# Arduino_Nano_with_7_segment_display.net
KiCad netlist of a schematic drawn in EAGLE
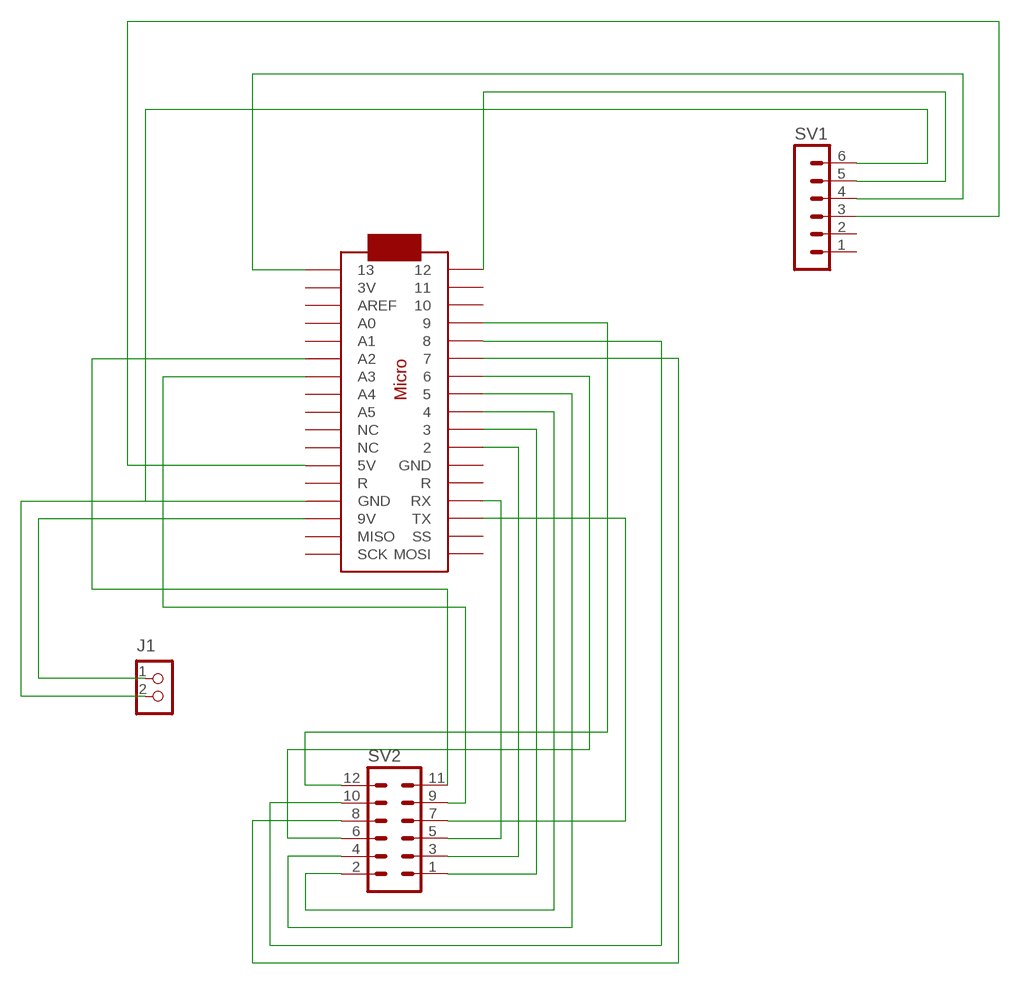
[diagram p0: schematic, sheet 1]

(export (version "E")
  (design (tool "Eeschema 10.0.6"))
  (components
    (comp (ref "J1")
      (value "CON_TERMINAL_BLOCK_02-5MM")
      (footprint "eagle-import:TERMINAL_BLOCK_2P_5")
      (libsource (lib "eagle-import") (part "CON_TERMINAL_BLOCK_02-5MM"))
    )
    (comp (ref "SV1")
      (value "MA06-1")
      (footprint "eagle-import:MA06-1")
      (libsource (lib "eagle-import") (part "MA06-1"))
    )
    (comp (ref "SV2")
      (value "MA06-2")
      (footprint "eagle-import:MA06-2")
      (libsource (lib "eagle-import") (part "MA06-2"))
    )
    (comp (ref "U$1")
      (value "ARDUINOMICRO")
      (footprint "eagle-import:ARDUINOMICRO")
      (libsource (lib "eagle-import") (part "ARDUINOMICRO"))
    )
  )
  (nets
    (net (code "1") (name "Net-(J1-Pad2)") (class "Default")
      (node (ref "J1") (pin "2") (pinfunction "2_2") (pintype "passive"))
      (node (ref "SV1") (pin "6") (pinfunction "6_6") (pintype "passive"))
      (node (ref "U$1") (pin "P$12") (pinfunction "GND_P$12") (pintype "bidirectional"))
    )
    (net (code "2") (name "Net-(U$1-2)") (class "Default")
      (node (ref "SV2") (pin "3") (pinfunction "3_3") (pintype "passive"))
      (node (ref "U$1") (pin "P$11") (pinfunction "2_P$11") (pintype "bidirectional"))
    )
    (net (code "3") (name "Net-(U$1-3)") (class "Default")
      (node (ref "SV2") (pin "1") (pinfunction "1_1") (pintype "passive"))
      (node (ref "U$1") (pin "P$10") (pinfunction "3_P$10") (pintype "bidirectional"))
    )
    (net (code "4") (name "Net-(U$1-4)") (class "Default")
      (node (ref "SV2") (pin "2") (pinfunction "2_2") (pintype "passive"))
      (node (ref "U$1") (pin "P$9") (pinfunction "4_P$9") (pintype "bidirectional"))
    )
    (net (code "5") (name "Net-(U$1-5)") (class "Default")
      (node (ref "SV2") (pin "4") (pinfunction "4_4") (pintype "passive"))
      (node (ref "U$1") (pin "P$8") (pinfunction "5_P$8") (pintype "bidirectional"))
    )
    (net (code "6") (name "Net-(U$1-5V)") (class "Default")
      (node (ref "SV1") (pin "3") (pinfunction "3_3") (pintype "passive"))
      (node (ref "U$1") (pin "P$23") (pinfunction "5V_P$23") (pintype "bidirectional"))
    )
    (net (code "7") (name "Net-(U$1-6)") (class "Default")
      (node (ref "SV2") (pin "6") (pinfunction "6_6") (pintype "passive"))
      (node (ref "U$1") (pin "P$7") (pinfunction "6_P$7") (pintype "bidirectional"))
    )
    (net (code "8") (name "Net-(U$1-7)") (class "Default")
      (node (ref "SV2") (pin "8") (pinfunction "8_8") (pintype "passive"))
      (node (ref "U$1") (pin "P$6") (pinfunction "7_P$6") (pintype "bidirectional"))
    )
    (net (code "9") (name "Net-(U$1-8)") (class "Default")
      (node (ref "SV2") (pin "10") (pinfunction "10_10") (pintype "passive"))
      (node (ref "U$1") (pin "P$5") (pinfunction "8_P$5") (pintype "bidirectional"))
    )
    (net (code "10") (name "Net-(U$1-9)") (class "Default")
      (node (ref "SV2") (pin "12") (pinfunction "12_12") (pintype "passive"))
      (node (ref "U$1") (pin "P$4") (pinfunction "9_P$4") (pintype "bidirectional"))
    )
    (net (code "11") (name "Net-(U$1-9V)") (class "Default")
      (node (ref "J1") (pin "1") (pinfunction "1_1") (pintype "passive"))
      (node (ref "U$1") (pin "P$20") (pinfunction "9V_P$20") (pintype "bidirectional"))
    )
    (net (code "12") (name "Net-(U$1-12)") (class "Default")
      (node (ref "SV1") (pin "5") (pinfunction "5_5") (pintype "passive"))
      (node (ref "U$1") (pin "P$1") (pinfunction "12_P$1") (pintype "bidirectional"))
    )
    (net (code "13") (name "Net-(U$1-13)") (class "Default")
      (node (ref "SV1") (pin "4") (pinfunction "4_4") (pintype "passive"))
      (node (ref "U$1") (pin "P$34") (pinfunction "13_P$34") (pintype "bidirectional"))
    )
    (net (code "14") (name "Net-(U$1-A2)") (class "Default")
      (node (ref "SV2") (pin "11") (pinfunction "11_11") (pintype "passive"))
      (node (ref "U$1") (pin "P$29") (pinfunction "A2_P$29") (pintype "bidirectional"))
    )
    (net (code "15") (name "Net-(U$1-A3)") (class "Default")
      (node (ref "SV2") (pin "9") (pinfunction "9_9") (pintype "passive"))
      (node (ref "U$1") (pin "P$28") (pinfunction "A3_P$28") (pintype "bidirectional"))
    )
    (net (code "16") (name "Net-(U$1-RX)") (class "Default")
      (node (ref "SV2") (pin "5") (pinfunction "5_5") (pintype "passive"))
      (node (ref "U$1") (pin "P$14") (pinfunction "RX_P$14") (pintype "bidirectional"))
    )
    (net (code "17") (name "Net-(U$1-TX)") (class "Default")
      (node (ref "SV2") (pin "7") (pinfunction "7_7") (pintype "passive"))
      (node (ref "U$1") (pin "P$15") (pinfunction "TX_P$15") (pintype "bidirectional"))
    )
    (net (code "18") (name "unconnected-(SV1-Pad1)") (class "Default")
      (node (ref "SV1") (pin "1") (pinfunction "1_1") (pintype "passive"))
    )
    (net (code "19") (name "unconnected-(SV1-Pad2)") (class "Default")
      (node (ref "SV1") (pin "2") (pinfunction "2_2") (pintype "passive"))
    )
    (net (code "20") (name "unconnected-(U$1-3V-PadP$33)") (class "Default")
      (node (ref "U$1") (pin "P$33") (pinfunction "3V_P$33") (pintype "bidirectional"))
    )
    (net (code "21") (name "unconnected-(U$1-10-PadP$3)") (class "Default")
      (node (ref "U$1") (pin "P$3") (pinfunction "10_P$3") (pintype "bidirectional"))
    )
    (net (code "22") (name "unconnected-(U$1-11-PadP$2)") (class "Default")
      (node (ref "U$1") (pin "P$2") (pinfunction "11_P$2") (pintype "bidirectional"))
    )
    (net (code "23") (name "unconnected-(U$1-A0-PadP$31)") (class "Default")
      (node (ref "U$1") (pin "P$31") (pinfunction "A0_P$31") (pintype "bidirectional"))
    )
    (net (code "24") (name "unconnected-(U$1-A1-PadP$30)") (class "Default")
      (node (ref "U$1") (pin "P$30") (pinfunction "A1_P$30") (pintype "bidirectional"))
    )
    (net (code "25") (name "unconnected-(U$1-A4-PadP$27)") (class "Default")
      (node (ref "U$1") (pin "P$27") (pinfunction "A4_P$27") (pintype "bidirectional"))
    )
    (net (code "26") (name "unconnected-(U$1-A5-PadP$26)") (class "Default")
      (node (ref "U$1") (pin "P$26") (pinfunction "A5_P$26") (pintype "bidirectional"))
    )
    (net (code "27") (name "unconnected-(U$1-AREF-PadP$32)") (class "Default")
      (node (ref "U$1") (pin "P$32") (pinfunction "AREF_P$32") (pintype "bidirectional"))
    )
    (net (code "28") (name "unconnected-(U$1-GND-PadP$21)") (class "Default")
      (node (ref "U$1") (pin "P$21") (pinfunction "GND_P$21") (pintype "bidirectional"))
    )
    (net (code "29") (name "unconnected-(U$1-MISO-PadP$19)") (class "Default")
      (node (ref "U$1") (pin "P$19") (pinfunction "MISO_P$19") (pintype "bidirectional"))
    )
    (net (code "30") (name "unconnected-(U$1-MOSI-PadP$17)") (class "Default")
      (node (ref "U$1") (pin "P$17") (pinfunction "MOSI_P$17") (pintype "bidirectional"))
    )
    (net (code "31") (name "unconnected-(U$1-NC-PadP$24)") (class "Default")
      (node (ref "U$1") (pin "P$24") (pinfunction "NC_P$24") (pintype "bidirectional"))
    )
    (net (code "32") (name "unconnected-(U$1-NC-PadP$25)") (class "Default")
      (node (ref "U$1") (pin "P$25") (pinfunction "NC_P$25") (pintype "bidirectional"))
    )
    (net (code "33") (name "unconnected-(U$1-R-PadP$13)") (class "Default")
      (node (ref "U$1") (pin "P$13") (pinfunction "R_P$13") (pintype "bidirectional"))
    )
    (net (code "34") (name "unconnected-(U$1-R-PadP$22)") (class "Default")
      (node (ref "U$1") (pin "P$22") (pinfunction "R_P$22") (pintype "bidirectional"))
    )
    (net (code "35") (name "unconnected-(U$1-SCK-PadP$18)") (class "Default")
      (node (ref "U$1") (pin "P$18") (pinfunction "SCK_P$18") (pintype "bidirectional"))
    )
    (net (code "36") (name "unconnected-(U$1-SS-PadP$16)") (class "Default")
      (node (ref "U$1") (pin "P$16") (pinfunction "SS_P$16") (pintype "bidirectional"))
    )
  )
)
